# OSU_Robotics_Kids.net
KiCad netlist of a schematic drawn in Altium Designer
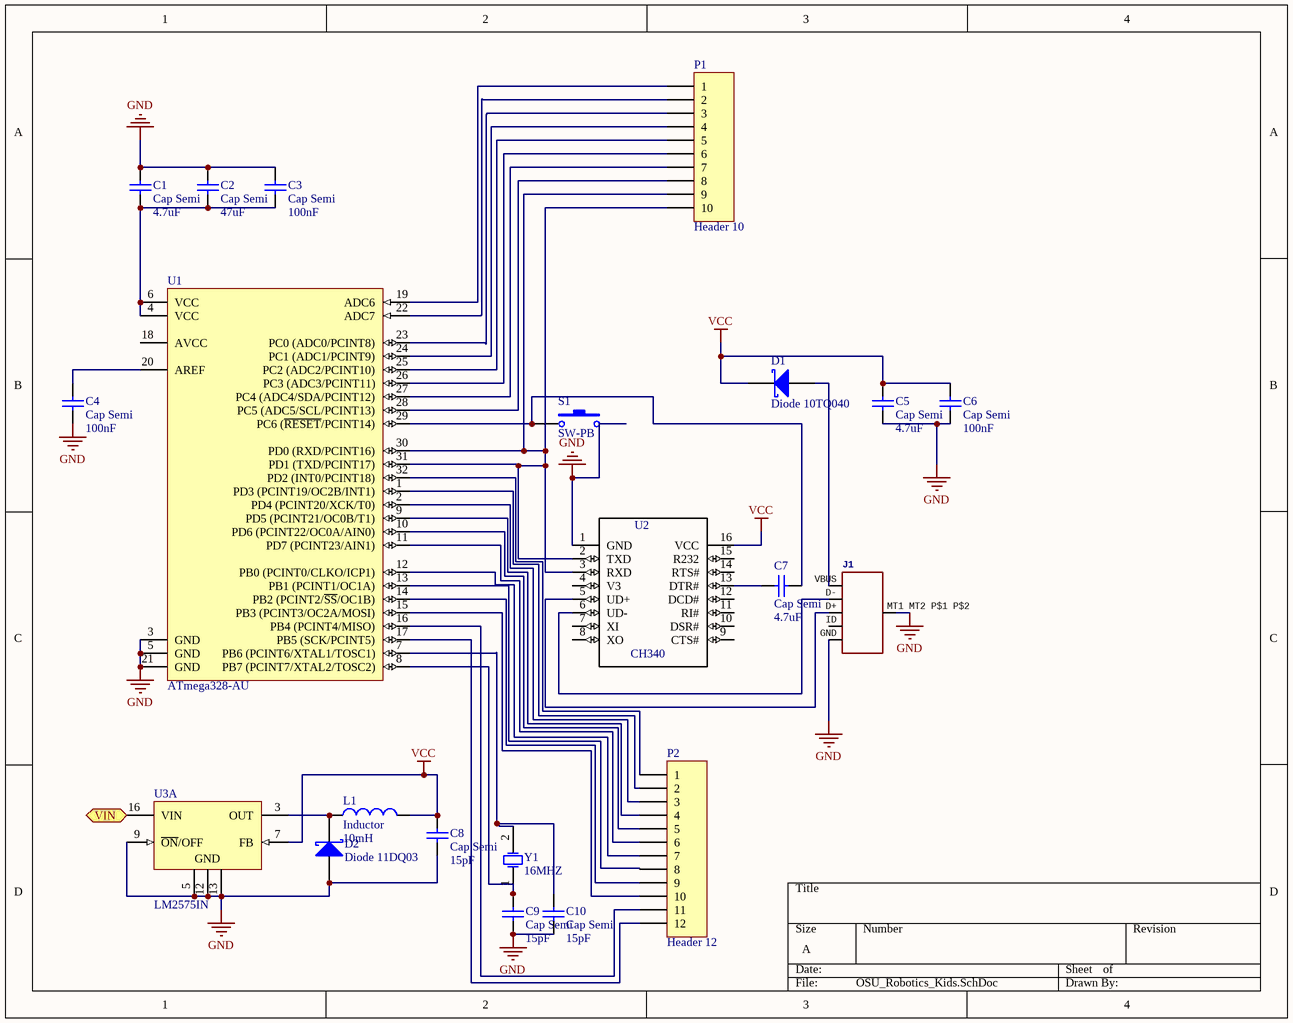
[diagram p0: OSU_Robotics_Kids.SchDoc]

(export (version "E")
  (design (tool "Eeschema 10.0.6"))
  (components
    (comp (ref "C1")
      (value "Cap Semi")
      (footprint "C1206")
      (description "Capacitor (Semiconductor SIM Model)")
      (fields (field (name "ALTIUM_VALUE") "4.7uF") (field (name "PUBLISHER") "Altium Limited"))
      (libsource (lib "Miscellaneous Devices") (part "Cap Semi"))
    )
    (comp (ref "C2")
      (value "Cap Semi")
      (footprint "C1206")
      (description "Capacitor (Semiconductor SIM Model)")
      (fields (field (name "ALTIUM_VALUE") "47uF") (field (name "PUBLISHER") "Altium Limited"))
      (libsource (lib "Miscellaneous Devices") (part "Cap Semi"))
    )
    (comp (ref "C3")
      (value "Cap Semi")
      (footprint "C1206")
      (description "Capacitor (Semiconductor SIM Model)")
      (fields (field (name "ALTIUM_VALUE") "100nF") (field (name "PUBLISHER") "Altium Limited"))
      (libsource (lib "Miscellaneous Devices") (part "Cap Semi"))
    )
    (comp (ref "C4")
      (value "Cap Semi")
      (footprint "C1206")
      (description "Capacitor (Semiconductor SIM Model)")
      (fields (field (name "ALTIUM_VALUE") "100nF") (field (name "PUBLISHER") "Altium Limited"))
      (libsource (lib "Miscellaneous Devices") (part "Cap Semi"))
    )
    (comp (ref "C5")
      (value "Cap Semi")
      (footprint "C1206")
      (description "Capacitor (Semiconductor SIM Model)")
      (fields (field (name "ALTIUM_VALUE") "4.7uF") (field (name "PUBLISHER") "Altium Limited"))
      (libsource (lib "Miscellaneous Devices") (part "Cap Semi"))
    )
    (comp (ref "C6")
      (value "Cap Semi")
      (footprint "C1206")
      (description "Capacitor (Semiconductor SIM Model)")
      (fields (field (name "ALTIUM_VALUE") "100nF") (field (name "PUBLISHER") "Altium Limited"))
      (libsource (lib "Miscellaneous Devices") (part "Cap Semi"))
    )
    (comp (ref "C7")
      (value "Cap Semi")
      (footprint "C1206")
      (description "Capacitor (Semiconductor SIM Model)")
      (fields (field (name "ALTIUM_VALUE") "4.7uF") (field (name "PUBLISHER") "Altium Limited"))
      (libsource (lib "Miscellaneous Devices") (part "Cap Semi"))
    )
    (comp (ref "C8")
      (value "Cap Semi")
      (footprint "C1206")
      (description "Capacitor (Semiconductor SIM Model)")
      (fields (field (name "ALTIUM_VALUE") "15pF") (field (name "PUBLISHER") "Altium Limited"))
      (libsource (lib "Miscellaneous Devices") (part "Cap Semi"))
    )
    (comp (ref "C9")
      (value "Cap Semi")
      (footprint "C1206")
      (description "Capacitor (Semiconductor SIM Model)")
      (fields (field (name "ALTIUM_VALUE") "15pF") (field (name "PUBLISHER") "Altium Limited"))
      (libsource (lib "Miscellaneous Devices") (part "Cap Semi"))
    )
    (comp (ref "C10")
      (value "Cap Semi")
      (footprint "C1206")
      (description "Capacitor (Semiconductor SIM Model)")
      (fields (field (name "ALTIUM_VALUE") "15pF") (field (name "PUBLISHER") "Altium Limited"))
      (libsource (lib "Miscellaneous Devices") (part "Cap Semi"))
    )
    (comp (ref "D1")
      (value "Diode 10TQ040")
      (footprint "TO-220AC")
      (description "Schottky Rectifier")
      (fields (field (name "PUBLISHER") "Altium Limited"))
      (libsource (lib "Miscellaneous Devices") (part "Diode 10TQ040"))
    )
    (comp (ref "D2")
      (value "Diode 11DQ03")
      (footprint "DO-204AL")
      (description "Schottky Rectifier")
      (fields (field (name "PUBLISHER") "Altium Limited"))
      (libsource (lib "Miscellaneous Devices") (part "Diode 11DQ03"))
    )
    (comp (ref "J1")
      (value "~")
      (footprint "USB-MICROB")
      (libsource (lib "SparkFun-Connectors") (part "USB_MICRO-B_SMT"))
    )
    (comp (ref "L1")
      (value "Inductor")
      (footprint "INDC3216")
      (fields (field (name "ALTIUM_VALUE") "10mH") (field (name "PUBLISHER") "Altium Limited"))
      (libsource (lib "Miscellaneous Devices") (part "Inductor"))
    )
    (comp (ref "P1")
      (value "Header 10")
      (footprint "HDR1X10")
      (description "Header, 10-Pin")
      (fields (field (name "PUBLISHER") "Altium Limited"))
      (libsource (lib "Miscellaneous Connectors") (part "Header 10"))
    )
    (comp (ref "P2")
      (value "Header 12")
      (footprint "HDR1X12")
      (description "Header, 12-Pin")
      (fields (field (name "PUBLISHER") "Altium Limited"))
      (libsource (lib "Miscellaneous Connectors") (part "Header 12"))
    )
    (comp (ref "S1")
      (value "SW-PB")
      (footprint "SPST-2")
      (description "Switch")
      (fields (field (name "PUBLISHER") "Altium Limited"))
      (libsource (lib "Miscellaneous Devices") (part "SW-PB"))
    )
    (comp (ref "U1")
      (value "ATmega328-AU")
      (footprint "32A_N")
      (libsource (lib "Atmel Microcontroller megaAVR") (part "ATmega328-AU"))
    )
    (comp (ref "U2")
      (value "CH340")
      (footprint "SO16")
      (description "Eaton / Cutler Hammer CH340 Circuit Breaker 40 Amp 240 Volt AC 3-Pole Plug-On Mount")
      (fields (field (name "MF") "Eaton / Cutler Hammer"))
      (libsource (lib "CH340") (part "CH340"))
    )
    (comp (ref "U3")
      (value "LM2575IN")
      (footprint "N16")
      (fields (field (name "MANUFACTURER") "Texas Instruments"))
      (libsource (lib "TI Power Management Step-Down Regulator") (part "LM2575IN"))
    )
    (comp (ref "Y1")
      (value "16MHZ")
      (footprint "R38")
      (description "Crystal Oscillator")
      (fields (field (name "PUBLISHER") "Altium Limited"))
      (libsource (lib "Miscellaneous Devices") (part "XTAL"))
    )
  )
  (nets
    (net (code "1") (name "/VIN") (class "Default")
      (node (ref "U3") (pin "16") (pinfunction "VIN_16") (pintype "power_in"))
    )
    (net (code "2") (name "GND") (class "Default")
      (node (ref "C1") (pin "2") (pinfunction "2_2") (pintype "passive"))
      (node (ref "C10") (pin "1") (pinfunction "1_1") (pintype "passive"))
      (node (ref "C2") (pin "2") (pinfunction "2_2") (pintype "passive"))
      (node (ref "C3") (pin "2") (pinfunction "2_2") (pintype "passive"))
      (node (ref "C4") (pin "1") (pinfunction "1_1") (pintype "passive"))
      (node (ref "C5") (pin "1") (pinfunction "1_1") (pintype "passive"))
      (node (ref "C6") (pin "1") (pinfunction "1_1") (pintype "passive"))
      (node (ref "C8") (pin "1") (pinfunction "1_1") (pintype "passive"))
      (node (ref "C9") (pin "1") (pinfunction "1_1") (pintype "passive"))
      (node (ref "D2") (pin "1") (pinfunction "A_1") (pintype "passive"))
      (node (ref "J1") (pin "GND") (pinfunction "GND_GND") (pintype "power_in"))
      (node (ref "J1") (pin "MT1_MT2_P$1_P$2") (pinfunction "SHIELD_MT1_MT2_P$1_P$2") (pintype "passive"))
      (node (ref "S1") (pin "2") (pinfunction "2_2") (pintype "passive"))
      (node (ref "U1") (pin "21") (pinfunction "GND_21") (pintype "power_in"))
      (node (ref "U1") (pin "3") (pinfunction "GND_3") (pintype "power_in"))
      (node (ref "U1") (pin "5") (pinfunction "GND_5") (pintype "power_in"))
      (node (ref "U2") (pin "1") (pinfunction "GND_1") (pintype "power_in"))
      (node (ref "U3") (pin "12") (pinfunction "GND_12") (pintype "power_in"))
      (node (ref "U3") (pin "13") (pinfunction "GND_13") (pintype "power_in"))
      (node (ref "U3") (pin "5") (pinfunction "GND_5") (pintype "power_in"))
      (node (ref "U3") (pin "9") (pinfunction "~{ON}/OFF_9") (pintype "input"))
    )
    (net (code "3") (name "Net-(C1-Pad1)") (class "Default")
      (node (ref "C1") (pin "1") (pinfunction "1_1") (pintype "passive"))
      (node (ref "C2") (pin "1") (pinfunction "1_1") (pintype "passive"))
      (node (ref "C3") (pin "1") (pinfunction "1_1") (pintype "passive"))
      (node (ref "U1") (pin "4") (pinfunction "VCC_4") (pintype "power_in"))
      (node (ref "U1") (pin "6") (pinfunction "VCC_6") (pintype "power_in"))
    )
    (net (code "4") (name "Net-(D1-A)") (class "Default")
      (node (ref "D1") (pin "3") (pinfunction "A_3") (pintype "passive"))
      (node (ref "J1") (pin "VBUS") (pinfunction "VBUS_VBUS") (pintype "power_in"))
    )
    (net (code "5") (name "Net-(D2-K)") (class "Default")
      (node (ref "D2") (pin "2") (pinfunction "K_2") (pintype "passive"))
      (node (ref "L1") (pin "1") (pinfunction "1_1") (pintype "passive"))
      (node (ref "U3") (pin "3") (pinfunction "OUT_3") (pintype "power_in"))
    )
    (net (code "6") (name "Net-(U1-ADC6)") (class "Default")
      (node (ref "P1") (pin "1") (pinfunction "1_1") (pintype "passive"))
      (node (ref "U1") (pin "19") (pinfunction "ADC6_19") (pintype "input"))
    )
    (net (code "7") (name "Net-(U1-ADC7)") (class "Default")
      (node (ref "P1") (pin "2") (pinfunction "2_2") (pintype "passive"))
      (node (ref "U1") (pin "22") (pinfunction "ADC7_22") (pintype "input"))
    )
    (net (code "8") (name "Net-(U1-AREF)") (class "Default")
      (node (ref "C4") (pin "2") (pinfunction "2_2") (pintype "passive"))
      (node (ref "U1") (pin "20") (pinfunction "AREF_20") (pintype "passive"))
    )
    (net (code "9") (name "Net-(U1-PB0_(PCINT0{slash}CLKO{slash}ICP1))") (class "Default")
      (node (ref "P2") (pin "7") (pinfunction "7_7") (pintype "passive"))
      (node (ref "U1") (pin "12") (pinfunction "PB0_(PCINT0/CLKO/ICP1)_12") (pintype "bidirectional"))
    )
    (net (code "10") (name "Net-(U1-PB1_(PCINT1{slash}OC1A))") (class "Default")
      (node (ref "P2") (pin "8") (pinfunction "8_8") (pintype "passive"))
      (node (ref "U1") (pin "13") (pinfunction "PB1_(PCINT1/OC1A)_13") (pintype "bidirectional"))
    )
    (net (code "11") (name "Net-(U1-PB2_(PCINT2{slash}~{SS}{slash}OC1B))") (class "Default")
      (node (ref "P2") (pin "9") (pinfunction "9_9") (pintype "passive"))
      (node (ref "U1") (pin "14") (pinfunction "PB2_(PCINT2/~{SS}/OC1B)_14") (pintype "bidirectional"))
    )
    (net (code "12") (name "Net-(U1-PB3_(PCINT3{slash}OC2A{slash}MOSI))") (class "Default")
      (node (ref "P2") (pin "10") (pinfunction "10_10") (pintype "passive"))
      (node (ref "U1") (pin "15") (pinfunction "PB3_(PCINT3/OC2A/MOSI)_15") (pintype "bidirectional"))
    )
    (net (code "13") (name "Net-(U1-PB4_(PCINT4{slash}MISO))") (class "Default")
      (node (ref "P2") (pin "11") (pinfunction "11_11") (pintype "passive"))
      (node (ref "U1") (pin "16") (pinfunction "PB4_(PCINT4/MISO)_16") (pintype "bidirectional"))
    )
    (net (code "14") (name "Net-(U1-PB5_(SCK{slash}PCINT5))") (class "Default")
      (node (ref "P2") (pin "12") (pinfunction "12_12") (pintype "passive"))
      (node (ref "U1") (pin "17") (pinfunction "PB5_(SCK/PCINT5)_17") (pintype "bidirectional"))
    )
    (net (code "15") (name "Net-(U1-PB6_(PCINT6{slash}XTAL1{slash}TOSC1))") (class "Default")
      (node (ref "C10") (pin "2") (pinfunction "2_2") (pintype "passive"))
      (node (ref "U1") (pin "7") (pinfunction "PB6_(PCINT6/XTAL1/TOSC1)_7") (pintype "bidirectional"))
      (node (ref "Y1") (pin "2") (pinfunction "OSC2_2") (pintype "passive"))
    )
    (net (code "16") (name "Net-(U1-PB7_(PCINT7{slash}XTAL2{slash}TOSC2))") (class "Default")
      (node (ref "C9") (pin "2") (pinfunction "2_2") (pintype "passive"))
      (node (ref "U1") (pin "8") (pinfunction "PB7_(PCINT7/XTAL2/TOSC2)_8") (pintype "bidirectional"))
      (node (ref "Y1") (pin "1") (pinfunction "OSC1_1") (pintype "passive"))
    )
    (net (code "17") (name "Net-(U1-PC0_(ADC0{slash}PCINT8))") (class "Default")
      (node (ref "P1") (pin "3") (pinfunction "3_3") (pintype "passive"))
      (node (ref "U1") (pin "23") (pinfunction "PC0_(ADC0/PCINT8)_23") (pintype "bidirectional"))
    )
    (net (code "18") (name "Net-(U1-PC1_(ADC1{slash}PCINT9))") (class "Default")
      (node (ref "P1") (pin "4") (pinfunction "4_4") (pintype "passive"))
      (node (ref "U1") (pin "24") (pinfunction "PC1_(ADC1/PCINT9)_24") (pintype "bidirectional"))
    )
    (net (code "19") (name "Net-(U1-PC2_(ADC2{slash}PCINT10))") (class "Default")
      (node (ref "P1") (pin "5") (pinfunction "5_5") (pintype "passive"))
      (node (ref "U1") (pin "25") (pinfunction "PC2_(ADC2/PCINT10)_25") (pintype "bidirectional"))
    )
    (net (code "20") (name "Net-(U1-PC3_(ADC3{slash}PCINT11))") (class "Default")
      (node (ref "P1") (pin "6") (pinfunction "6_6") (pintype "passive"))
      (node (ref "U1") (pin "26") (pinfunction "PC3_(ADC3/PCINT11)_26") (pintype "bidirectional"))
    )
    (net (code "21") (name "Net-(U1-PC4_(ADC4{slash}SDA{slash}PCINT12))") (class "Default")
      (node (ref "P1") (pin "7") (pinfunction "7_7") (pintype "passive"))
      (node (ref "U1") (pin "27") (pinfunction "PC4_(ADC4/SDA/PCINT12)_27") (pintype "bidirectional"))
    )
    (net (code "22") (name "Net-(U1-PC5_(ADC5{slash}SCL{slash}PCINT13))") (class "Default")
      (node (ref "P1") (pin "8") (pinfunction "8_8") (pintype "passive"))
      (node (ref "U1") (pin "28") (pinfunction "PC5_(ADC5/SCL/PCINT13)_28") (pintype "bidirectional"))
    )
    (net (code "23") (name "Net-(U1-PC6_(~{RESET}{slash}PCINT14))") (class "Default")
      (node (ref "C7") (pin "1") (pinfunction "1_1") (pintype "passive"))
      (node (ref "S1") (pin "1") (pinfunction "1_1") (pintype "passive"))
      (node (ref "U1") (pin "29") (pinfunction "PC6_(~{RESET}/PCINT14)_29") (pintype "bidirectional"))
    )
    (net (code "24") (name "Net-(U1-PD0_(RXD{slash}PCINT16))") (class "Default")
      (node (ref "P1") (pin "10") (pinfunction "10_10") (pintype "passive"))
      (node (ref "P1") (pin "9") (pinfunction "9_9") (pintype "passive"))
      (node (ref "U1") (pin "30") (pinfunction "PD0_(RXD/PCINT16)_30") (pintype "bidirectional"))
      (node (ref "U1") (pin "31") (pinfunction "PD1_(TXD/PCINT17)_31") (pintype "bidirectional"))
      (node (ref "U2") (pin "2") (pinfunction "TXD_2") (pintype "bidirectional"))
      (node (ref "U2") (pin "3") (pinfunction "RXD_3") (pintype "bidirectional"))
    )
    (net (code "25") (name "Net-(U1-PD2_(INT0{slash}PCINT18))") (class "Default")
      (node (ref "P2") (pin "1") (pinfunction "1_1") (pintype "passive"))
      (node (ref "U1") (pin "32") (pinfunction "PD2_(INT0/PCINT18)_32") (pintype "bidirectional"))
    )
    (net (code "26") (name "Net-(U1-PD3_(PCINT19{slash}OC2B{slash}INT1))") (class "Default")
      (node (ref "P2") (pin "2") (pinfunction "2_2") (pintype "passive"))
      (node (ref "U1") (pin "1") (pinfunction "PD3_(PCINT19/OC2B/INT1)_1") (pintype "bidirectional"))
    )
    (net (code "27") (name "Net-(U1-PD4_(PCINT20{slash}XCK{slash}T0))") (class "Default")
      (node (ref "P2") (pin "3") (pinfunction "3_3") (pintype "passive"))
      (node (ref "U1") (pin "2") (pinfunction "PD4_(PCINT20/XCK/T0)_2") (pintype "bidirectional"))
    )
    (net (code "28") (name "Net-(U1-PD5_(PCINT21{slash}OC0B{slash}T1))") (class "Default")
      (node (ref "P2") (pin "4") (pinfunction "4_4") (pintype "passive"))
      (node (ref "U1") (pin "9") (pinfunction "PD5_(PCINT21/OC0B/T1)_9") (pintype "bidirectional"))
    )
    (net (code "29") (name "Net-(U1-PD6_(PCINT22{slash}OC0A{slash}AIN0))") (class "Default")
      (node (ref "P2") (pin "5") (pinfunction "5_5") (pintype "passive"))
      (node (ref "U1") (pin "10") (pinfunction "PD6_(PCINT22/OC0A/AIN0)_10") (pintype "bidirectional"))
    )
    (net (code "30") (name "Net-(U1-PD7_(PCINT23{slash}AIN1))") (class "Default")
      (node (ref "P2") (pin "6") (pinfunction "6_6") (pintype "passive"))
      (node (ref "U1") (pin "11") (pinfunction "PD7_(PCINT23/AIN1)_11") (pintype "bidirectional"))
    )
    (net (code "31") (name "Net-(U2-DTR#)") (class "Default")
      (node (ref "C7") (pin "2") (pinfunction "2_2") (pintype "passive"))
      (node (ref "U2") (pin "13") (pinfunction "DTR#_13") (pintype "bidirectional"))
    )
    (net (code "32") (name "Net-(U2-UD+)") (class "Default")
      (node (ref "J1") (pin "D+") (pinfunction "D+_D+") (pintype "passive"))
      (node (ref "U2") (pin "5") (pinfunction "UD+_5") (pintype "bidirectional"))
    )
    (net (code "33") (name "Net-(U2-UD-)") (class "Default")
      (node (ref "J1") (pin "D-") (pinfunction "D-_D-") (pintype "passive"))
      (node (ref "U2") (pin "6") (pinfunction "UD-_6") (pintype "bidirectional"))
    )
    (net (code "34") (name "VCC") (class "Default")
      (node (ref "C5") (pin "2") (pinfunction "2_2") (pintype "passive"))
      (node (ref "C6") (pin "2") (pinfunction "2_2") (pintype "passive"))
      (node (ref "C8") (pin "2") (pinfunction "2_2") (pintype "passive"))
      (node (ref "D1") (pin "1") (pinfunction "K_1") (pintype "passive"))
      (node (ref "L1") (pin "2") (pinfunction "2_2") (pintype "passive"))
      (node (ref "U2") (pin "16") (pinfunction "VCC_16") (pintype "power_in"))
      (node (ref "U3") (pin "7") (pinfunction "FB_7") (pintype "input"))
    )
    (net (code "35") (name "unconnected-(J1-PadID)") (class "Default")
      (node (ref "J1") (pin "ID") (pinfunction "ID_ID") (pintype "passive"))
    )
    (net (code "36") (name "unconnected-(U1-AVCC-Pad18)") (class "Default")
      (node (ref "U1") (pin "18") (pinfunction "AVCC_18") (pintype "power_in"))
    )
    (net (code "37") (name "unconnected-(U2-CTS#-Pad9)") (class "Default")
      (node (ref "U2") (pin "9") (pinfunction "CTS#_9") (pintype "bidirectional"))
    )
    (net (code "38") (name "unconnected-(U2-DCD#-Pad12)") (class "Default")
      (node (ref "U2") (pin "12") (pinfunction "DCD#_12") (pintype "bidirectional"))
    )
    (net (code "39") (name "unconnected-(U2-DSR#-Pad10)") (class "Default")
      (node (ref "U2") (pin "10") (pinfunction "DSR#_10") (pintype "bidirectional"))
    )
    (net (code "40") (name "unconnected-(U2-R232-Pad15)") (class "Default")
      (node (ref "U2") (pin "15") (pinfunction "R232_15") (pintype "bidirectional"))
    )
    (net (code "41") (name "unconnected-(U2-RI#-Pad11)") (class "Default")
      (node (ref "U2") (pin "11") (pinfunction "RI#_11") (pintype "bidirectional"))
    )
    (net (code "42") (name "unconnected-(U2-RTS#-Pad14)") (class "Default")
      (node (ref "U2") (pin "14") (pinfunction "RTS#_14") (pintype "bidirectional"))
    )
    (net (code "43") (name "unconnected-(U2-V3-Pad4)") (class "Default")
      (node (ref "U2") (pin "4") (pinfunction "V3_4") (pintype "bidirectional"))
    )
    (net (code "44") (name "unconnected-(U2-XI-Pad7)") (class "Default")
      (node (ref "U2") (pin "7") (pinfunction "XI_7") (pintype "bidirectional"))
    )
    (net (code "45") (name "unconnected-(U2-XO-Pad8)") (class "Default")
      (node (ref "U2") (pin "8") (pinfunction "XO_8") (pintype "bidirectional"))
    )
  )
)
